# OSO-SWAT-A1-02.net
KiCad netlist of a schematic drawn in EAGLE
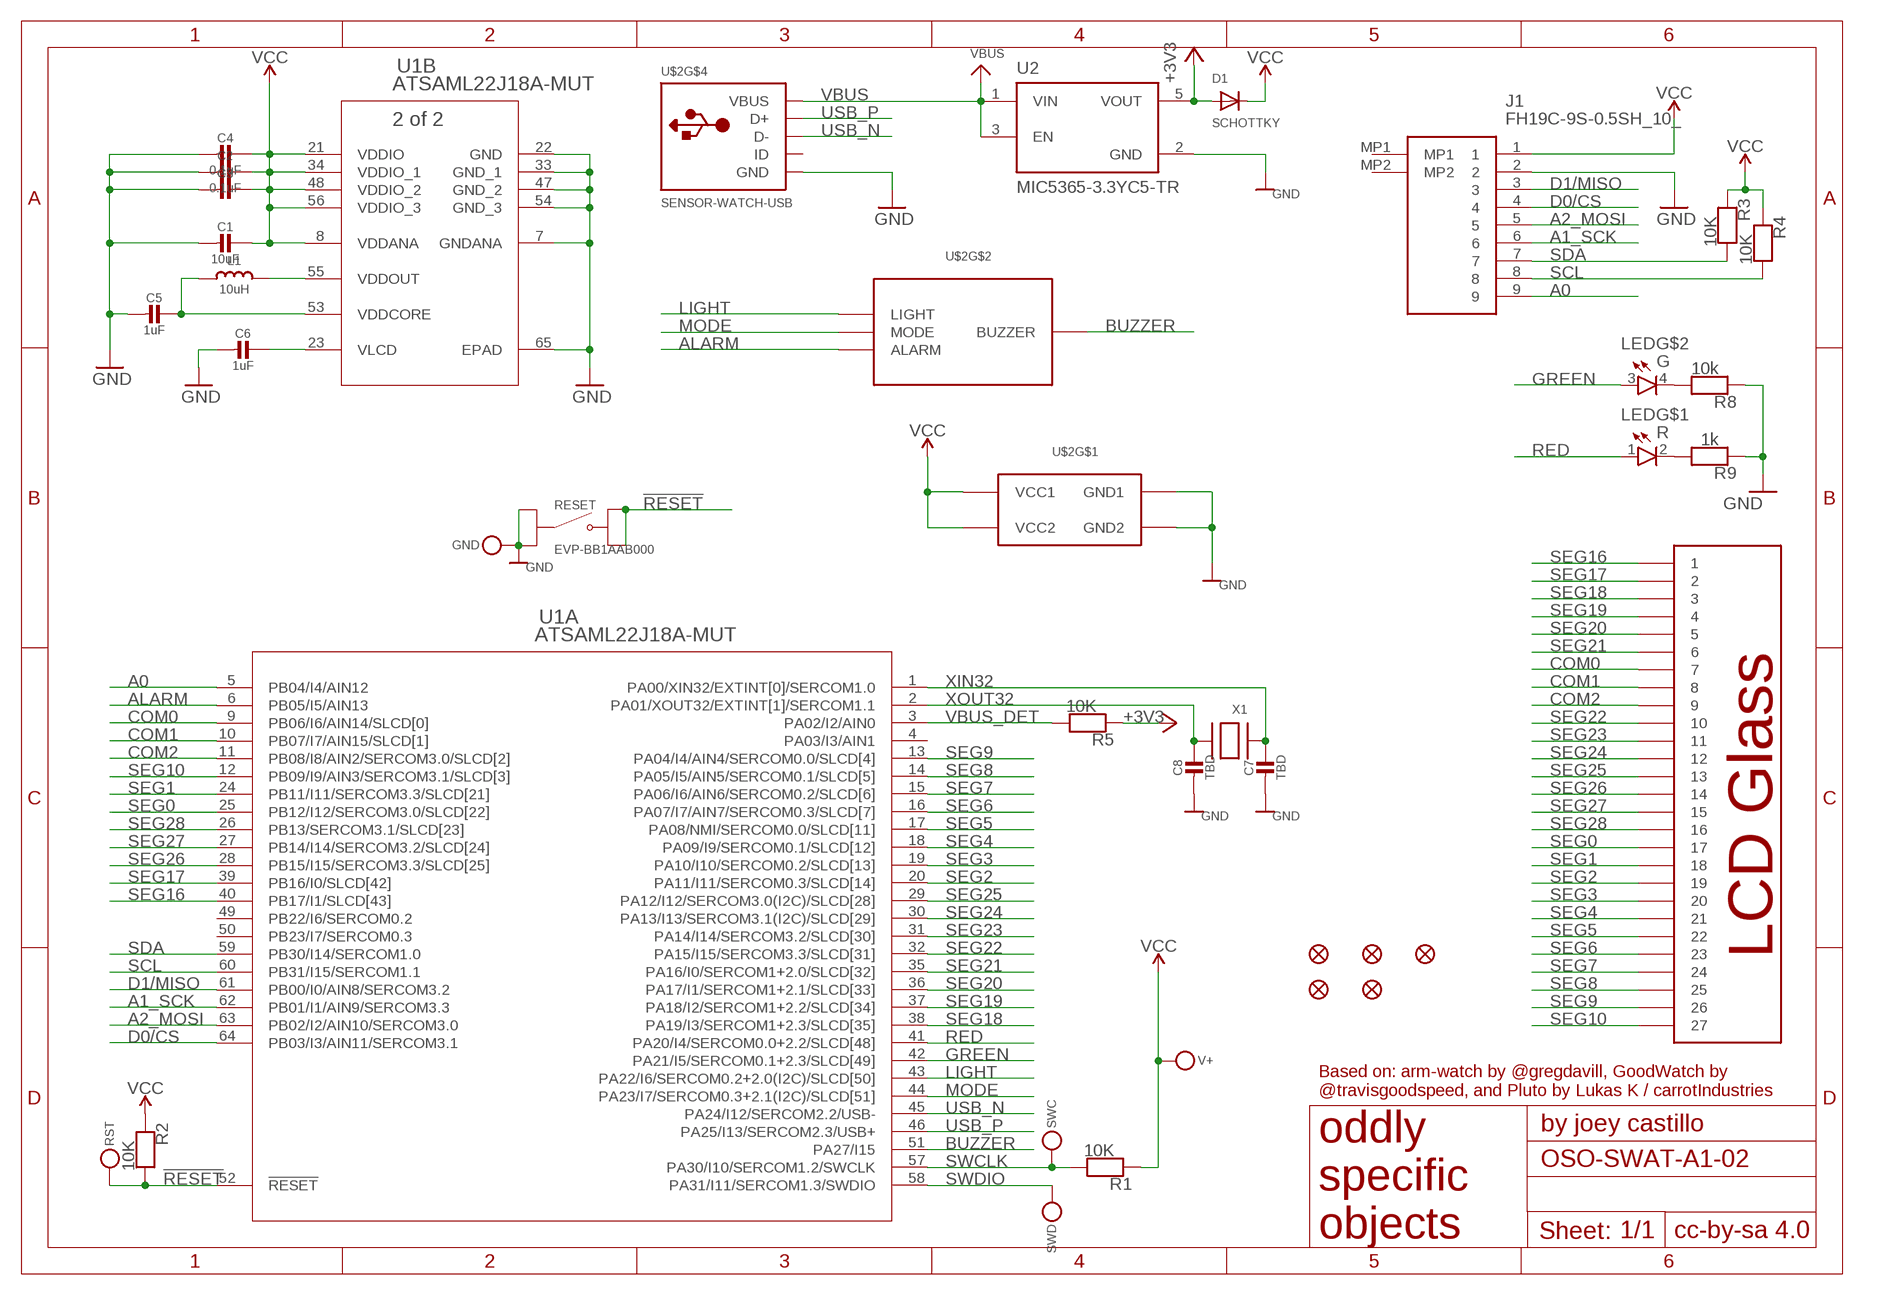
[diagram p0: schematic, sheet 1]

(export (version "E")
  (design (tool "Eeschema 10.0.6"))
  (components
    (comp (ref "C1")
      (value "10uF")
      (footprint "eagle-import:_0603MP")
      (libsource (lib "eagle-import") (part "CAP_CERAMIC_0603MP"))
    )
    (comp (ref "C2")
      (value "0.1uF")
      (footprint "eagle-import:_0603MP")
      (libsource (lib "eagle-import") (part "CAP_CERAMIC_0603MP"))
    )
    (comp (ref "C3")
      (value "0.1uF")
      (footprint "eagle-import:_0603MP")
      (libsource (lib "eagle-import") (part "CAP_CERAMIC_0603MP"))
    )
    (comp (ref "C4")
      (value "0.1uF")
      (footprint "eagle-import:_0603MP")
      (libsource (lib "eagle-import") (part "CAP_CERAMIC_0603MP"))
    )
    (comp (ref "C5")
      (value "1uF")
      (footprint "eagle-import:_0603MP")
      (libsource (lib "eagle-import") (part "CAP_CERAMIC_0603MP"))
    )
    (comp (ref "C6")
      (value "1uF")
      (footprint "eagle-import:_0603MP")
      (libsource (lib "eagle-import") (part "CAP_CERAMIC_0603MP"))
    )
    (comp (ref "C7")
      (value "TBD")
      (footprint "eagle-import:_0402MP")
      (libsource (lib "eagle-import") (part "CAP_CERAMIC_0402MP"))
    )
    (comp (ref "C8")
      (value "TBD")
      (footprint "eagle-import:_0402MP")
      (libsource (lib "eagle-import") (part "CAP_CERAMIC_0402MP"))
    )
    (comp (ref "D1")
      (value "SCHOTTKY")
      (footprint "eagle-import:SOD-323F")
      (libsource (lib "eagle-import") (part "DIODESOD-323F"))
    )
    (comp (ref "FID1")
      (value "FIDUCIAL_1MM")
      (footprint "eagle-import:FIDUCIAL_1MM")
      (libsource (lib "eagle-import") (part "FIDUCIAL_1MM"))
    )
    (comp (ref "FID2")
      (value "FIDUCIAL_1MM")
      (footprint "eagle-import:FIDUCIAL_1MM")
      (libsource (lib "eagle-import") (part "FIDUCIAL_1MM"))
    )
    (comp (ref "FID3")
      (value "FIDUCIAL_1MM")
      (footprint "eagle-import:FIDUCIAL_1MM")
      (fields (field (name "REV") "A"))
      (libsource (lib "eagle-import") (part "FIDUCIAL_1MM"))
    )
    (comp (ref "FID4")
      (value "FIDUCIAL_1MM")
      (footprint "eagle-import:FIDUCIAL_1MM")
      (libsource (lib "eagle-import") (part "FIDUCIAL_1MM"))
    )
    (comp (ref "FID6")
      (value "FIDUCIAL_1MM")
      (footprint "eagle-import:FIDUCIAL_1MM")
      (fields (field (name "REV") "A"))
      (libsource (lib "eagle-import") (part "FIDUCIAL_1MM"))
    )
    (comp (ref "GND")
      (value "MICROBUILDER_TESTPOINTROUND1.5MM")
      (footprint "eagle-import:MICROBUILDER_TESTPOINT_ROUND_1.5MM")
      (libsource (lib "eagle-import") (part "MICROBUILDER_TESTPOINTROUND1.5MM"))
    )
    (comp (ref "J1")
      (value "FH19C-9S-0.5SH_10_")
      (footprint "eagle-import:FH19C9S05SH10")
      (fields
        (field (name "MANUFACTURER_PART_NUMBER") "FH19C-9S-0.5SH(10)")
        (field (name "MOUSER_PART_NUMBER") "798-FH19C9S05SH10")
      )
      (libsource (lib "eagle-import") (part "FH19C-9S-0.5SH_10_"))
    )
    (comp (ref "L1")
      (value "10uH")
      (footprint "eagle-import:MICROBUILDER__0805MP")
      (libsource (lib "eagle-import") (part "MICROBUILDER_INDUCTOR_0805MP"))
    )
    (comp (ref "LED")
      (value "QBLP655R")
      (footprint "eagle-import:LED_QBLP655R")
      (fields
        (field (name "DIGI-KEY_PART_NUMBER") "160-2026-1-ND")
        (field (name "MF") "Lite-On Inc.")
        (field (name "MP") "LTST-C235KGKRKT")
      )
      (libsource (lib "eagle-import") (part "QBLP655R"))
    )
    (comp (ref "R1")
      (value "10K")
      (footprint "eagle-import:_0603MP")
      (libsource (lib "eagle-import") (part "RESISTOR_0603MP"))
    )
    (comp (ref "R2")
      (value "10K")
      (footprint "eagle-import:_0603MP")
      (libsource (lib "eagle-import") (part "RESISTOR_0603MP"))
    )
    (comp (ref "R3")
      (value "10K")
      (footprint "eagle-import:_0603MP")
      (libsource (lib "eagle-import") (part "RESISTOR_0603MP"))
    )
    (comp (ref "R4")
      (value "10K")
      (footprint "eagle-import:_0603MP")
      (libsource (lib "eagle-import") (part "RESISTOR_0603MP"))
    )
    (comp (ref "R5")
      (value "10K")
      (footprint "eagle-import:_0603MP")
      (libsource (lib "eagle-import") (part "RESISTOR_0603MP"))
    )
    (comp (ref "R8")
      (value "10k")
      (footprint "eagle-import:_0603MP")
      (libsource (lib "eagle-import") (part "RESISTOR_0603MP"))
    )
    (comp (ref "R9")
      (value "1k")
      (footprint "eagle-import:_0603MP")
      (libsource (lib "eagle-import") (part "RESISTOR_0603MP"))
    )
    (comp (ref "RESET")
      (value "EVP-BB1AAB000")
      (footprint "eagle-import:SW_EVP-BB1AAB000")
      (fields
        (field (name "DIGI-KEY_PART_NUMBER") "P124390CT-ND")
        (field (name "MF") "Panasonic Electronic Components")
      )
      (libsource (lib "eagle-import") (part "EVP-BB1AAB000"))
    )
    (comp (ref "RST")
      (value "MICROBUILDER_TESTPOINTROUND1.5MM")
      (footprint "eagle-import:MICROBUILDER_TESTPOINT_ROUND_1.5MM")
      (libsource (lib "eagle-import") (part "MICROBUILDER_TESTPOINTROUND1.5MM"))
    )
    (comp (ref "SWC")
      (value "MICROBUILDER_TESTPOINTROUND1.5MM")
      (footprint "eagle-import:MICROBUILDER_TESTPOINT_ROUND_1.5MM")
      (libsource (lib "eagle-import") (part "MICROBUILDER_TESTPOINTROUND1.5MM"))
    )
    (comp (ref "SWD")
      (value "MICROBUILDER_TESTPOINTROUND1.5MM")
      (footprint "eagle-import:MICROBUILDER_TESTPOINT_ROUND_1.5MM")
      (libsource (lib "eagle-import") (part "MICROBUILDER_TESTPOINTROUND1.5MM"))
    )
    (comp (ref "U$2")
      (value "SENSOR-WATCH-USB")
      (footprint "eagle-import:CASIO-F91W-OUTLINE-USB")
      (libsource (lib "eagle-import") (part "SENSOR-WATCH-USB"))
    )
    (comp (ref "U1")
      (value "ATSAML22J18A-MUT")
      (footprint "eagle-import:QFN64_9X9MC_MCH")
      (fields (field (name "COPYRIGHT") "Copyright (C) 2018 Accelerated Designs. All rights reserved"))
      (libsource (lib "eagle-import") (part "ATSAML22J18A-MUT"))
    )
    (comp (ref "U2")
      (value "MIC5365-3.3YC5-TR")
      (footprint "eagle-import:SOT65P210X110-5N")
      (fields (field (name "DIGI-KEY_PART_NUMBER") "576-3193-1-ND") (field (name "MF") "Microchip"))
      (libsource (lib "eagle-import") (part "MIC5365-3.3YC5-TR"))
    )
    (comp (ref "V+")
      (value "MICROBUILDER_TESTPOINTROUND1.5MM")
      (footprint "eagle-import:MICROBUILDER_TESTPOINT_ROUND_1.5MM")
      (libsource (lib "eagle-import") (part "MICROBUILDER_TESTPOINTROUND1.5MM"))
    )
    (comp (ref "X1")
      (value "XTAL-3.2X1.5")
      (footprint "eagle-import:XTAL3215")
      (libsource (lib "eagle-import") (part "XTAL-3.2X1.5"))
    )
  )
  (nets
    (net (code "1") (name "+3V3") (class "Default")
      (node (ref "D1") (pin "A") (pinfunction "A_A") (pintype "passive"))
      (node (ref "R5") (pin "1") (pinfunction "1_1") (pintype "passive"))
      (node (ref "U2") (pin "5") (pinfunction "VOUT_5") (pintype "output"))
    )
    (net (code "2") (name "/A0") (class "Default")
      (node (ref "J1") (pin "9") (pinfunction "9_9") (pintype "bidirectional"))
      (node (ref "U1") (pin "5") (pinfunction "PB04/I4/AIN12_5") (pintype "bidirectional"))
    )
    (net (code "3") (name "/A1_SCK") (class "Default")
      (node (ref "J1") (pin "6") (pinfunction "6_6") (pintype "bidirectional"))
      (node (ref "U1") (pin "62") (pinfunction "PB01/I1/AIN9/SERCOM3.3_62") (pintype "bidirectional"))
    )
    (net (code "4") (name "/A2_MOSI") (class "Default")
      (node (ref "J1") (pin "5") (pinfunction "5_5") (pintype "bidirectional"))
      (node (ref "U1") (pin "63") (pinfunction "PB02/I2/AIN10/SERCOM3.0_63") (pintype "bidirectional"))
    )
    (net (code "5") (name "/ALARM") (class "Default")
      (node (ref "U$2") (pin "ALARM") (pinfunction "ALARM_ALARM") (pintype "bidirectional"))
      (node (ref "U1") (pin "6") (pinfunction "PB05/I5/AIN13_6") (pintype "bidirectional"))
    )
    (net (code "6") (name "/BUZZER") (class "Default")
      (node (ref "U$2") (pin "BUZZER") (pinfunction "BUZZER_BUZZER") (pintype "bidirectional"))
      (node (ref "U1") (pin "51") (pinfunction "PA27/I15_51") (pintype "bidirectional"))
    )
    (net (code "7") (name "/COM0") (class "Default")
      (node (ref "U$2") (pin "7") (pinfunction "7_7") (pintype "input"))
      (node (ref "U1") (pin "9") (pinfunction "PB06/I6/AIN14/SLCD[0]_9") (pintype "bidirectional"))
    )
    (net (code "8") (name "/COM1") (class "Default")
      (node (ref "U$2") (pin "8") (pinfunction "8_8") (pintype "input"))
      (node (ref "U1") (pin "10") (pinfunction "PB07/I7/AIN15/SLCD[1]_10") (pintype "bidirectional"))
    )
    (net (code "9") (name "/COM2") (class "Default")
      (node (ref "U$2") (pin "9") (pinfunction "9_9") (pintype "input"))
      (node (ref "U1") (pin "11") (pinfunction "PB08/I8/AIN2/SERCOM3.0/SLCD[2]_11") (pintype "bidirectional"))
    )
    (net (code "10") (name "/D0{slash}CS") (class "Default")
      (node (ref "J1") (pin "4") (pinfunction "4_4") (pintype "bidirectional"))
      (node (ref "U1") (pin "64") (pinfunction "PB03/I3/AIN11/SERCOM3.1_64") (pintype "bidirectional"))
    )
    (net (code "11") (name "/D1{slash}MISO") (class "Default")
      (node (ref "J1") (pin "3") (pinfunction "3_3") (pintype "bidirectional"))
      (node (ref "U1") (pin "61") (pinfunction "PB00/I0/AIN8/SERCOM3.2_61") (pintype "bidirectional"))
    )
    (net (code "12") (name "/GREEN") (class "Default")
      (node (ref "LED") (pin "3") (pinfunction "A_3") (pintype "passive"))
      (node (ref "U1") (pin "42") (pinfunction "PA21/I5/SERCOM0.1+2.3/SLCD[49]_42") (pintype "bidirectional"))
    )
    (net (code "13") (name "/LIGHT") (class "Default")
      (node (ref "U$2") (pin "LIGHT") (pinfunction "LIGHT_LIGHT") (pintype "bidirectional"))
      (node (ref "U1") (pin "43") (pinfunction "PA22/I6/SERCOM0.2+2.0(I2C)/SLCD[50]_43") (pintype "bidirectional"))
    )
    (net (code "14") (name "/MODE") (class "Default")
      (node (ref "U$2") (pin "MODE") (pinfunction "MODE_MODE") (pintype "bidirectional"))
      (node (ref "U1") (pin "44") (pinfunction "PA23/I7/SERCOM0.3+2.1(I2C)/SLCD[51]_44") (pintype "bidirectional"))
    )
    (net (code "15") (name "/RED") (class "Default")
      (node (ref "LED") (pin "1") (pinfunction "A_1") (pintype "passive"))
      (node (ref "U1") (pin "41") (pinfunction "PA20/I4/SERCOM0.0+2.2/SLCD[48]_41") (pintype "bidirectional"))
    )
    (net (code "16") (name "/SCL") (class "Default")
      (node (ref "J1") (pin "8") (pinfunction "8_8") (pintype "bidirectional"))
      (node (ref "R4") (pin "2") (pinfunction "2_2") (pintype "passive"))
      (node (ref "U1") (pin "60") (pinfunction "PB31/I15/SERCOM1.1_60") (pintype "bidirectional"))
    )
    (net (code "17") (name "/SDA") (class "Default")
      (node (ref "J1") (pin "7") (pinfunction "7_7") (pintype "bidirectional"))
      (node (ref "R3") (pin "2") (pinfunction "2_2") (pintype "passive"))
      (node (ref "U1") (pin "59") (pinfunction "PB30/I14/SERCOM1.0_59") (pintype "bidirectional"))
    )
    (net (code "18") (name "/SEG0") (class "Default")
      (node (ref "U$2") (pin "17") (pinfunction "17_17") (pintype "input"))
      (node (ref "U1") (pin "25") (pinfunction "PB12/I12/SERCOM3.0/SLCD[22]_25") (pintype "bidirectional"))
    )
    (net (code "19") (name "/SEG1") (class "Default")
      (node (ref "U$2") (pin "18") (pinfunction "18_18") (pintype "input"))
      (node (ref "U1") (pin "24") (pinfunction "PB11/I11/SERCOM3.3/SLCD[21]_24") (pintype "bidirectional"))
    )
    (net (code "20") (name "/SEG2") (class "Default")
      (node (ref "U$2") (pin "19") (pinfunction "19_19") (pintype "input"))
      (node (ref "U1") (pin "20") (pinfunction "PA11/I11/SERCOM0.3/SLCD[14]_20") (pintype "bidirectional"))
    )
    (net (code "21") (name "/SEG3") (class "Default")
      (node (ref "U$2") (pin "20") (pinfunction "20_20") (pintype "input"))
      (node (ref "U1") (pin "19") (pinfunction "PA10/I10/SERCOM0.2/SLCD[13]_19") (pintype "bidirectional"))
    )
    (net (code "22") (name "/SEG4") (class "Default")
      (node (ref "U$2") (pin "21") (pinfunction "21_21") (pintype "input"))
      (node (ref "U1") (pin "18") (pinfunction "PA09/I9/SERCOM0.1/SLCD[12]_18") (pintype "bidirectional"))
    )
    (net (code "23") (name "/SEG5") (class "Default")
      (node (ref "U$2") (pin "22") (pinfunction "22_22") (pintype "input"))
      (node (ref "U1") (pin "17") (pinfunction "PA08/NMI/SERCOM0.0/SLCD[11]_17") (pintype "bidirectional"))
    )
    (net (code "24") (name "/SEG6") (class "Default")
      (node (ref "U$2") (pin "23") (pinfunction "23_23") (pintype "input"))
      (node (ref "U1") (pin "16") (pinfunction "PA07/I7/AIN7/SERCOM0.3/SLCD[7]_16") (pintype "bidirectional"))
    )
    (net (code "25") (name "/SEG7") (class "Default")
      (node (ref "U$2") (pin "24") (pinfunction "24_24") (pintype "input"))
      (node (ref "U1") (pin "15") (pinfunction "PA06/I6/AIN6/SERCOM0.2/SLCD[6]_15") (pintype "bidirectional"))
    )
    (net (code "26") (name "/SEG8") (class "Default")
      (node (ref "U$2") (pin "25") (pinfunction "25_25") (pintype "input"))
      (node (ref "U1") (pin "14") (pinfunction "PA05/I5/AIN5/SERCOM0.1/SLCD[5]_14") (pintype "bidirectional"))
    )
    (net (code "27") (name "/SEG9") (class "Default")
      (node (ref "U$2") (pin "26") (pinfunction "26_26") (pintype "input"))
      (node (ref "U1") (pin "13") (pinfunction "PA04/I4/AIN4/SERCOM0.0/SLCD[4]_13") (pintype "bidirectional"))
    )
    (net (code "28") (name "/SEG10") (class "Default")
      (node (ref "U$2") (pin "27") (pinfunction "27_27") (pintype "input"))
      (node (ref "U1") (pin "12") (pinfunction "PB09/I9/AIN3/SERCOM3.1/SLCD[3]_12") (pintype "bidirectional"))
    )
    (net (code "29") (name "/SEG16") (class "Default")
      (node (ref "U$2") (pin "1") (pinfunction "1_1") (pintype "input"))
      (node (ref "U1") (pin "40") (pinfunction "PB17/I1/SLCD[43]_40") (pintype "bidirectional"))
    )
    (net (code "30") (name "/SEG17") (class "Default")
      (node (ref "U$2") (pin "2") (pinfunction "2_2") (pintype "input"))
      (node (ref "U1") (pin "39") (pinfunction "PB16/I0/SLCD[42]_39") (pintype "bidirectional"))
    )
    (net (code "31") (name "/SEG18") (class "Default")
      (node (ref "U$2") (pin "3") (pinfunction "3_3") (pintype "input"))
      (node (ref "U1") (pin "38") (pinfunction "PA19/I3/SERCOM1+2.3/SLCD[35]_38") (pintype "bidirectional"))
    )
    (net (code "32") (name "/SEG19") (class "Default")
      (node (ref "U$2") (pin "4") (pinfunction "4_4") (pintype "input"))
      (node (ref "U1") (pin "37") (pinfunction "PA18/I2/SERCOM1+2.2/SLCD[34]_37") (pintype "bidirectional"))
    )
    (net (code "33") (name "/SEG20") (class "Default")
      (node (ref "U$2") (pin "5") (pinfunction "5_5") (pintype "input"))
      (node (ref "U1") (pin "36") (pinfunction "PA17/I1/SERCOM1+2.1/SLCD[33]_36") (pintype "bidirectional"))
    )
    (net (code "34") (name "/SEG21") (class "Default")
      (node (ref "U$2") (pin "6") (pinfunction "6_6") (pintype "input"))
      (node (ref "U1") (pin "35") (pinfunction "PA16/I0/SERCOM1+2.0/SLCD[32]_35") (pintype "bidirectional"))
    )
    (net (code "35") (name "/SEG22") (class "Default")
      (node (ref "U$2") (pin "10") (pinfunction "10_10") (pintype "input"))
      (node (ref "U1") (pin "32") (pinfunction "PA15/I15/SERCOM3.3/SLCD[31]_32") (pintype "bidirectional"))
    )
    (net (code "36") (name "/SEG23") (class "Default")
      (node (ref "U$2") (pin "11") (pinfunction "11_11") (pintype "input"))
      (node (ref "U1") (pin "31") (pinfunction "PA14/I14/SERCOM3.2/SLCD[30]_31") (pintype "bidirectional"))
    )
    (net (code "37") (name "/SEG24") (class "Default")
      (node (ref "U$2") (pin "12") (pinfunction "12_12") (pintype "input"))
      (node (ref "U1") (pin "30") (pinfunction "PA13/I13/SERCOM3.1(I2C)/SLCD[29]_30") (pintype "bidirectional"))
    )
    (net (code "38") (name "/SEG25") (class "Default")
      (node (ref "U$2") (pin "13") (pinfunction "13_13") (pintype "input"))
      (node (ref "U1") (pin "29") (pinfunction "PA12/I12/SERCOM3.0(I2C)/SLCD[28]_29") (pintype "bidirectional"))
    )
    (net (code "39") (name "/SEG26") (class "Default")
      (node (ref "U$2") (pin "14") (pinfunction "14_14") (pintype "input"))
      (node (ref "U1") (pin "28") (pinfunction "PB15/I15/SERCOM3.3/SLCD[25]_28") (pintype "bidirectional"))
    )
    (net (code "40") (name "/SEG27") (class "Default")
      (node (ref "U$2") (pin "15") (pinfunction "15_15") (pintype "input"))
      (node (ref "U1") (pin "27") (pinfunction "PB14/I14/SERCOM3.2/SLCD[24]_27") (pintype "bidirectional"))
    )
    (net (code "41") (name "/SEG28") (class "Default")
      (node (ref "U$2") (pin "16") (pinfunction "16_16") (pintype "input"))
      (node (ref "U1") (pin "26") (pinfunction "PB13/SERCOM3.1/SLCD[23]_26") (pintype "bidirectional"))
    )
    (net (code "42") (name "/SWCLK") (class "Default")
      (node (ref "R1") (pin "2") (pinfunction "2_2") (pintype "passive"))
      (node (ref "SWC") (pin "P$1") (pinfunction "P$1_P$1") (pintype "bidirectional"))
      (node (ref "U1") (pin "57") (pinfunction "PA30/I10/SERCOM1.2/SWCLK_57") (pintype "bidirectional"))
    )
    (net (code "43") (name "/SWDIO") (class "Default")
      (node (ref "SWD") (pin "P$1") (pinfunction "P$1_P$1") (pintype "bidirectional"))
      (node (ref "U1") (pin "58") (pinfunction "PA31/I11/SERCOM1.3/SWDIO_58") (pintype "bidirectional"))
    )
    (net (code "44") (name "/USB_N") (class "Default")
      (node (ref "U$2") (pin "USB_N") (pinfunction "D-_USB_N") (pintype "bidirectional"))
      (node (ref "U1") (pin "45") (pinfunction "PA24/I12/SERCOM2.2/USB-_45") (pintype "bidirectional"))
    )
    (net (code "45") (name "/USB_P") (class "Default")
      (node (ref "U$2") (pin "USB_P") (pinfunction "D+_USB_P") (pintype "bidirectional"))
      (node (ref "U1") (pin "46") (pinfunction "PA25/I13/SERCOM2.3/USB+_46") (pintype "bidirectional"))
    )
    (net (code "46") (name "/VBUS_DET") (class "Default")
      (node (ref "R5") (pin "2") (pinfunction "2_2") (pintype "passive"))
      (node (ref "U1") (pin "3") (pinfunction "PA02/I2/AIN0_3") (pintype "bidirectional"))
    )
    (net (code "47") (name "/XIN32") (class "Default")
      (node (ref "C7") (pin "1") (pinfunction "1_1") (pintype "passive"))
      (node (ref "U1") (pin "1") (pinfunction "PA00/XIN32/EXTINT[0]/SERCOM1.0_1") (pintype "bidirectional"))
      (node (ref "X1") (pin "P$1") (pinfunction "P$1_P$1") (pintype "bidirectional"))
    )
    (net (code "48") (name "/XOUT32") (class "Default")
      (node (ref "C8") (pin "1") (pinfunction "1_1") (pintype "passive"))
      (node (ref "U1") (pin "2") (pinfunction "PA01/XOUT32/EXTINT[1]/SERCOM1.1_2") (pintype "bidirectional"))
      (node (ref "X1") (pin "P$2") (pinfunction "P$2_P$2") (pintype "bidirectional"))
    )
    (net (code "49") (name "/~{RESET}") (class "Default")
      (node (ref "R2") (pin "2") (pinfunction "2_2") (pintype "passive"))
      (node (ref "RESET") (pin "B1") (pinfunction "B1_B1") (pintype "passive"))
      (node (ref "RESET") (pin "B2") (pinfunction "B2_B2") (pintype "passive"))
      (node (ref "RST") (pin "P$1") (pinfunction "P$1_P$1") (pintype "bidirectional"))
      (node (ref "U1") (pin "52") (pinfunction "~{RESET}_52") (pintype "bidirectional"))
    )
    (net (code "50") (name "GND") (class "Default")
      (node (ref "C1") (pin "2") (pinfunction "2_2") (pintype "passive"))
      (node (ref "C2") (pin "2") (pinfunction "2_2") (pintype "passive"))
      (node (ref "C3") (pin "2") (pinfunction "2_2") (pintype "passive"))
      (node (ref "C4") (pin "2") (pinfunction "2_2") (pintype "passive"))
      (node (ref "C5") (pin "2") (pinfunction "2_2") (pintype "passive"))
      (node (ref "C6") (pin "2") (pinfunction "2_2") (pintype "passive"))
      (node (ref "C7") (pin "2") (pinfunction "2_2") (pintype "passive"))
      (node (ref "C8") (pin "2") (pinfunction "2_2") (pintype "passive"))
      (node (ref "GND") (pin "P$1") (pinfunction "P$1_P$1") (pintype "bidirectional"))
      (node (ref "J1") (pin "2") (pinfunction "2_2") (pintype "bidirectional"))
      (node (ref "R8") (pin "1") (pinfunction "1_1") (pintype "passive"))
      (node (ref "R9") (pin "1") (pinfunction "1_1") (pintype "passive"))
      (node (ref "RESET") (pin "A1") (pinfunction "A1_A1") (pintype "passive"))
      (node (ref "RESET") (pin "A2") (pinfunction "A2_A2") (pintype "passive"))
      (node (ref "U$2") (pin "GND") (pinfunction "GND_GND") (pintype "power_in"))
      (node (ref "U$2") (pin "GND1") (pinfunction "GND1_GND1") (pintype "bidirectional"))
      (node (ref "U$2") (pin "GND2") (pinfunction "GND2_GND2") (pintype "bidirectional"))
      (node (ref "U1") (pin "22") (pinfunction "GND_22") (pintype "passive"))
      (node (ref "U1") (pin "33") (pinfunction "GND_1_33") (pintype "passive"))
      (node (ref "U1") (pin "47") (pinfunction "GND_2_47") (pintype "passive"))
      (node (ref "U1") (pin "54") (pinfunction "GND_3_54") (pintype "passive"))
      (node (ref "U1") (pin "65") (pinfunction "EPAD_65") (pintype "passive"))
      (node (ref "U1") (pin "7") (pinfunction "GNDANA_7") (pintype "passive"))
      (node (ref "U2") (pin "2") (pinfunction "GND_2") (pintype "power_in"))
    )
    (net (code "51") (name "Net-(LEDA-C)") (class "Default")
      (node (ref "LED") (pin "2") (pinfunction "C_2") (pintype "passive"))
      (node (ref "R9") (pin "2") (pinfunction "2_2") (pintype "passive"))
    )
    (net (code "52") (name "Net-(LEDB-C)") (class "Default")
      (node (ref "LED") (pin "4") (pinfunction "C_4") (pintype "passive"))
      (node (ref "R8") (pin "2") (pinfunction "2_2") (pintype "passive"))
    )
    (net (code "53") (name "Net-(U1B-VDDCORE)") (class "Default")
      (node (ref "C5") (pin "1") (pinfunction "1_1") (pintype "passive"))
      (node (ref "L1") (pin "1") (pinfunction "1_1") (pintype "passive"))
      (node (ref "U1") (pin "53") (pinfunction "VDDCORE_53") (pintype "power_in"))
    )
    (net (code "54") (name "Net-(U1B-VDDOUT)") (class "Default")
      (node (ref "L1") (pin "2") (pinfunction "2_2") (pintype "passive"))
      (node (ref "U1") (pin "55") (pinfunction "VDDOUT_55") (pintype "output"))
    )
    (net (code "55") (name "Net-(U1B-VLCD)") (class "Default")
      (node (ref "C6") (pin "1") (pinfunction "1_1") (pintype "passive"))
      (node (ref "U1") (pin "23") (pinfunction "VLCD_23") (pintype "passive"))
    )
    (net (code "56") (name "VBUS") (class "Default")
      (node (ref "U$2") (pin "VBUS") (pinfunction "VBUS_VBUS") (pintype "power_in"))
      (node (ref "U2") (pin "1") (pinfunction "VIN_1") (pintype "input"))
      (node (ref "U2") (pin "3") (pinfunction "EN_3") (pintype "input"))
    )
    (net (code "57") (name "VCC") (class "Default")
      (node (ref "C1") (pin "1") (pinfunction "1_1") (pintype "passive"))
      (node (ref "C2") (pin "1") (pinfunction "1_1") (pintype "passive"))
      (node (ref "C3") (pin "1") (pinfunction "1_1") (pintype "passive"))
      (node (ref "C4") (pin "1") (pinfunction "1_1") (pintype "passive"))
      (node (ref "D1") (pin "C") (pinfunction "C_C") (pintype "passive"))
      (node (ref "J1") (pin "1") (pinfunction "1_1") (pintype "bidirectional"))
      (node (ref "R1") (pin "1") (pinfunction "1_1") (pintype "passive"))
      (node (ref "R2") (pin "1") (pinfunction "1_1") (pintype "passive"))
      (node (ref "R3") (pin "1") (pinfunction "1_1") (pintype "passive"))
      (node (ref "R4") (pin "1") (pinfunction "1_1") (pintype "passive"))
      (node (ref "U$2") (pin "VCC1") (pinfunction "VCC1_VCC1") (pintype "bidirectional"))
      (node (ref "U$2") (pin "VCC2") (pinfunction "VCC2_VCC2") (pintype "bidirectional"))
      (node (ref "U1") (pin "21") (pinfunction "VDDIO_21") (pintype "power_in"))
      (node (ref "U1") (pin "34") (pinfunction "VDDIO_1_34") (pintype "power_in"))
      (node (ref "U1") (pin "48") (pinfunction "VDDIO_2_48") (pintype "power_in"))
      (node (ref "U1") (pin "56") (pinfunction "VDDIO_3_56") (pintype "power_in"))
      (node (ref "U1") (pin "8") (pinfunction "VDDANA_8") (pintype "power_in"))
      (node (ref "V+") (pin "P$1") (pinfunction "P$1_P$1") (pintype "bidirectional"))
    )
    (net (code "58") (name "unconnected-(J1-PadMP1)") (class "Default")
      (node (ref "J1") (pin "MP1") (pinfunction "MP1_MP1") (pintype "bidirectional"))
    )
    (net (code "59") (name "unconnected-(J1-PadMP2)") (class "Default")
      (node (ref "J1") (pin "MP2") (pinfunction "MP2_MP2") (pintype "bidirectional"))
    )
    (net (code "60") (name "unconnected-(U$2D-ID-PadUSB_ID)") (class "Default")
      (node (ref "U$2") (pin "USB_ID") (pinfunction "ID_USB_ID") (pintype "bidirectional"))
    )
    (net (code "61") (name "unconnected-(U1A-PA03{slash}I3{slash}AIN1-Pad4)") (class "Default")
      (node (ref "U1") (pin "4") (pinfunction "PA03/I3/AIN1_4") (pintype "bidirectional"))
    )
    (net (code "62") (name "unconnected-(U1A-PB22{slash}I6{slash}SERCOM0.2-Pad49)") (class "Default")
      (node (ref "U1") (pin "49") (pinfunction "PB22/I6/SERCOM0.2_49") (pintype "bidirectional"))
    )
    (net (code "63") (name "unconnected-(U1A-PB23{slash}I7{slash}SERCOM0.3-Pad50)") (class "Default")
      (node (ref "U1") (pin "50") (pinfunction "PB23/I7/SERCOM0.3_50") (pintype "bidirectional"))
    )
  )
)
